# rain_ALARM.net
KiCad netlist of a schematic drawn in EAGLE
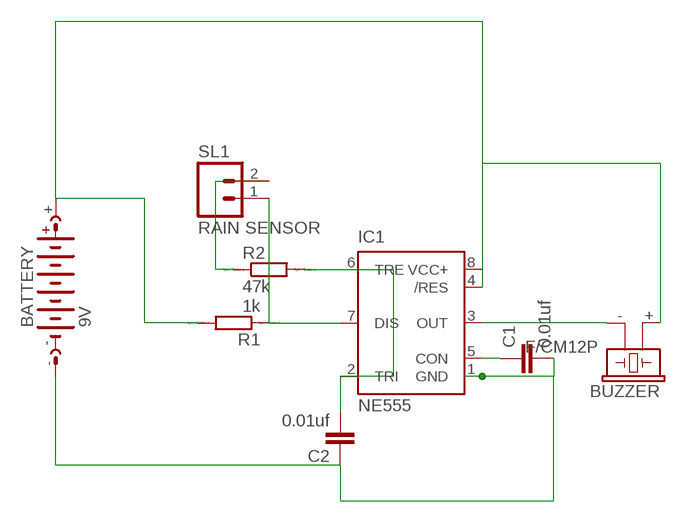
[diagram p0: schematic, sheet 1]

(export (version "E")
  (design (tool "Eeschema 10.0.6"))
  (components
    (comp (ref "BATTERY")
      (value "9V")
      (footprint "eagle-import:AB9V")
      (libsource (lib "eagle-import") (part "AB9V"))
    )
    (comp (ref "BUZZER")
      (value "F/CM12P")
      (footprint "eagle-import:F_CM12P")
      (libsource (lib "eagle-import") (part "F/CM12P"))
    )
    (comp (ref "C1")
      (value "0.01uf")
      (footprint "eagle-import:C2.5-5")
      (libsource (lib "eagle-import") (part "C2.5/5"))
    )
    (comp (ref "C2")
      (value "0.01uf")
      (footprint "eagle-import:C2.5-5")
      (libsource (lib "eagle-import") (part "C2.5/5"))
    )
    (comp (ref "IC1")
      (value "NE555")
      (footprint "eagle-import:DIL-08")
      (fields (field (name "MF") "Arrow Electronics") (field (name "MPN") "NE555N"))
      (libsource (lib "eagle-import") (part "NE555"))
    )
    (comp (ref "R1")
      (value "1k")
      (footprint "eagle-import:0204_7")
      (libsource (lib "eagle-import") (part "R0204/7"))
    )
    (comp (ref "R2")
      (value "47k")
      (footprint "eagle-import:0204_7")
      (libsource (lib "eagle-import") (part "R0204/7"))
    )
    (comp (ref "SL1")
      (value "RAIN SENSOR")
      (footprint "eagle-import:02P")
      (libsource (lib "eagle-import") (part "M02"))
    )
  )
  (nets
    (net (code "1") (name "Net-(BUZZER-1)") (class "Default")
      (node (ref "BATTERY") (pin "+") (pinfunction "+_+") (pintype "passive"))
      (node (ref "BUZZER") (pin "+") (pinfunction "1_+") (pintype "passive"))
      (node (ref "IC1") (pin "4") (pinfunction "/RES_4") (pintype "input"))
      (node (ref "IC1") (pin "8") (pinfunction "VCC+_8") (pintype "power_in"))
      (node (ref "R1") (pin "2") (pinfunction "2_2") (pintype "passive"))
    )
    (net (code "2") (name "Net-(BUZZER-2)") (class "Default")
      (node (ref "BUZZER") (pin "-") (pinfunction "2_-") (pintype "passive"))
      (node (ref "IC1") (pin "3") (pinfunction "OUT_3") (pintype "output"))
    )
    (net (code "3") (name "Net-(IC1-CON)") (class "Default")
      (node (ref "C1") (pin "1") (pinfunction "1_1") (pintype "passive"))
      (node (ref "IC1") (pin "5") (pinfunction "CON_5") (pintype "input"))
    )
    (net (code "4") (name "Net-(IC1-DIS)") (class "Default")
      (node (ref "IC1") (pin "7") (pinfunction "DIS_7") (pintype "input"))
      (node (ref "R1") (pin "1") (pinfunction "1_1") (pintype "passive"))
      (node (ref "SL1") (pin "1") (pinfunction "1_1") (pintype "passive"))
    )
    (net (code "5") (name "Net-(IC1-GND)") (class "Default")
      (node (ref "BATTERY") (pin "-") (pinfunction "-_-") (pintype "passive"))
      (node (ref "C1") (pin "2") (pinfunction "2_2") (pintype "passive"))
      (node (ref "C2") (pin "1") (pinfunction "1_1") (pintype "passive"))
      (node (ref "IC1") (pin "1") (pinfunction "GND_1") (pintype "power_in"))
    )
    (net (code "6") (name "Net-(IC1-TRE)") (class "Default")
      (node (ref "C2") (pin "2") (pinfunction "2_2") (pintype "passive"))
      (node (ref "IC1") (pin "2") (pinfunction "TRI_2") (pintype "input"))
      (node (ref "IC1") (pin "6") (pinfunction "TRE_6") (pintype "input"))
      (node (ref "R2") (pin "2") (pinfunction "2_2") (pintype "passive"))
    )
    (net (code "7") (name "Net-(R2-Pad1)") (class "Default")
      (node (ref "R2") (pin "1") (pinfunction "1_1") (pintype "passive"))
      (node (ref "SL1") (pin "2") (pinfunction "2_2") (pintype "passive"))
    )
  )
)
